# power_distribution_3_16_17.net
KiCad netlist of a schematic drawn in EAGLE
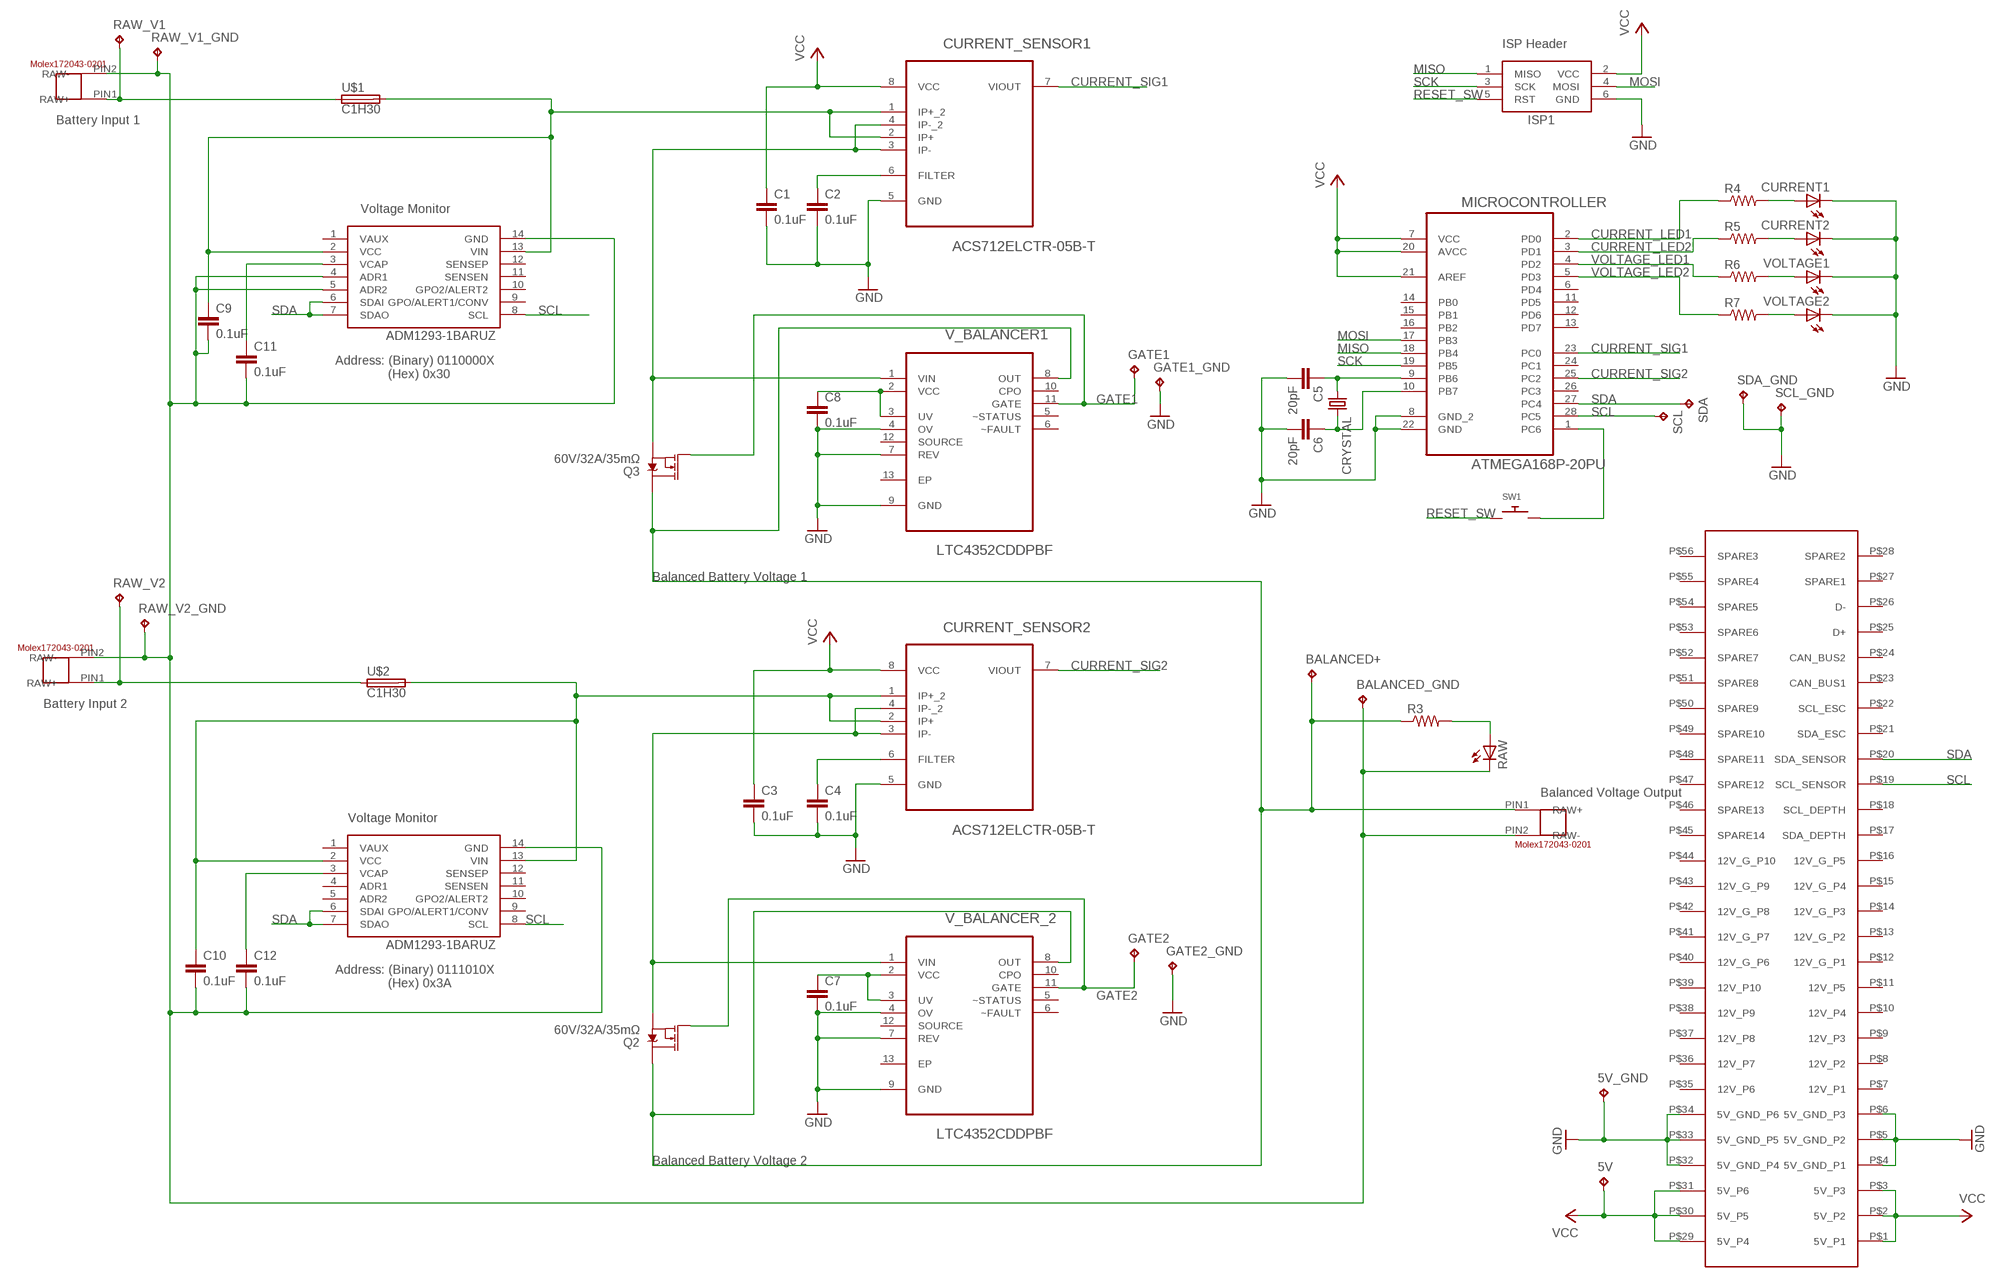
[diagram p0: schematic, sheet 1]

(export (version "E")
  (design (tool "Eeschema 10.0.6"))
  (components
    (comp (ref "5V")
      (value "TPPAD1-13")
      (footprint "eagle-import:P1-13")
      (libsource (lib "eagle-import") (part "TPPAD1-13"))
    )
    (comp (ref "5V_GND")
      (value "TPPAD1-13")
      (footprint "eagle-import:P1-13")
      (libsource (lib "eagle-import") (part "TPPAD1-13"))
    )
    (comp (ref "BALANCED+")
      (value "TPPAD1-13")
      (footprint "eagle-import:P1-13")
      (libsource (lib "eagle-import") (part "TPPAD1-13"))
    )
    (comp (ref "BALANCED_GND")
      (value "TPPAD1-13")
      (footprint "eagle-import:P1-13")
      (libsource (lib "eagle-import") (part "TPPAD1-13"))
    )
    (comp (ref "C1")
      (value "0.1uF")
      (footprint "eagle-import:CAP-PTH-SMALL-KIT")
      (libsource (lib "eagle-import") (part "0.1UF-KIT-EZ-50V-20%"))
    )
    (comp (ref "C2")
      (value "0.1uF")
      (footprint "eagle-import:CAP-PTH-SMALL-KIT")
      (libsource (lib "eagle-import") (part "0.1UF-KIT-EZ-50V-20%"))
    )
    (comp (ref "C3")
      (value "0.1uF")
      (footprint "eagle-import:CAP-PTH-SMALL-KIT")
      (libsource (lib "eagle-import") (part "0.1UF-KIT-EZ-50V-20%"))
    )
    (comp (ref "C4")
      (value "0.1uF")
      (footprint "eagle-import:CAP-PTH-SMALL-KIT")
      (libsource (lib "eagle-import") (part "0.1UF-KIT-EZ-50V-20%"))
    )
    (comp (ref "C5")
      (value "20pF")
      (footprint "eagle-import:CAP-PTH-SMALL-KIT")
      (libsource (lib "eagle-import") (part "0.1UF-KIT-EZ-50V-20%"))
    )
    (comp (ref "C6")
      (value "20pF")
      (footprint "eagle-import:CAP-PTH-SMALL-KIT")
      (libsource (lib "eagle-import") (part "0.1UF-KIT-EZ-50V-20%"))
    )
    (comp (ref "C7")
      (value "0.1uF")
      (footprint "eagle-import:CAP-PTH-SMALL-KIT")
      (libsource (lib "eagle-import") (part "0.1UF-KIT-EZ-50V-20%"))
    )
    (comp (ref "C8")
      (value "0.1uF")
      (footprint "eagle-import:CAP-PTH-SMALL-KIT")
      (libsource (lib "eagle-import") (part "0.1UF-KIT-EZ-50V-20%"))
    )
    (comp (ref "C9")
      (value "0.1uF")
      (footprint "eagle-import:CAP-PTH-SMALL-KIT")
      (libsource (lib "eagle-import") (part "0.1UF-KIT-EZ-50V-20%"))
    )
    (comp (ref "C10")
      (value "0.1uF")
      (footprint "eagle-import:CAP-PTH-SMALL-KIT")
      (libsource (lib "eagle-import") (part "0.1UF-KIT-EZ-50V-20%"))
    )
    (comp (ref "C11")
      (value "0.1uF")
      (footprint "eagle-import:CAP-PTH-SMALL-KIT")
      (libsource (lib "eagle-import") (part "0.1UF-KIT-EZ-50V-20%"))
    )
    (comp (ref "C12")
      (value "0.1uF")
      (footprint "eagle-import:CAP-PTH-SMALL-KIT")
      (libsource (lib "eagle-import") (part "0.1UF-KIT-EZ-50V-20%"))
    )
    (comp (ref "CRYSTAL")
      (value "CRYSTALHC49U-V")
      (footprint "eagle-import:HC49U-V")
      (libsource (lib "eagle-import") (part "CRYSTALHC49U-V"))
    )
    (comp (ref "CURRENT1")
      (value "LED3MM")
      (footprint "eagle-import:LED3MM")
      (libsource (lib "eagle-import") (part "LED3MM"))
    )
    (comp (ref "CURRENT2")
      (value "LED3MM")
      (footprint "eagle-import:LED3MM")
      (libsource (lib "eagle-import") (part "LED3MM"))
    )
    (comp (ref "CURRENT_SENSOR1")
      (value "ACS712ELCTR-05B-T")
      (footprint "eagle-import:SOIC127P600X175-8N")
      (libsource (lib "eagle-import") (part "ACS712ELCTR-05B-T"))
    )
    (comp (ref "CURRENT_SENSOR2")
      (value "ACS712ELCTR-05B-T")
      (footprint "eagle-import:SOIC127P600X175-8N")
      (libsource (lib "eagle-import") (part "ACS712ELCTR-05B-T"))
    )
    (comp (ref "GATE1")
      (value "TPPAD1-13")
      (footprint "eagle-import:P1-13")
      (libsource (lib "eagle-import") (part "TPPAD1-13"))
    )
    (comp (ref "GATE1_GND")
      (value "TPPAD1-13")
      (footprint "eagle-import:P1-13")
      (libsource (lib "eagle-import") (part "TPPAD1-13"))
    )
    (comp (ref "GATE2")
      (value "TPPAD1-13")
      (footprint "eagle-import:P1-13")
      (libsource (lib "eagle-import") (part "TPPAD1-13"))
    )
    (comp (ref "GATE2_GND")
      (value "TPPAD1-13")
      (footprint "eagle-import:P1-13")
      (libsource (lib "eagle-import") (part "TPPAD1-13"))
    )
    (comp (ref "INPUT1")
      (value "MOLEX172043-0201")
      (footprint "eagle-import:MOLEX172043-0201")
      (libsource (lib "eagle-import") (part "MOLEX172043-0201"))
    )
    (comp (ref "INPUT2")
      (value "MOLEX172043-0201")
      (footprint "eagle-import:MOLEX172043-0201")
      (libsource (lib "eagle-import") (part "MOLEX172043-0201"))
    )
    (comp (ref "ISP1")
      (value "AVRISP-6")
      (footprint "eagle-import:AVRISP")
      (libsource (lib "eagle-import") (part "AVRISP-6"))
    )
    (comp (ref "MICROCONTROLLER")
      (value "ATMEGA168P-20PU")
      (footprint "eagle-import:DIP254P762X457-28")
      (libsource (lib "eagle-import") (part "ATMEGA168P-20PU"))
    )
    (comp (ref "OUTPUT")
      (value "MOLEX172043-0201")
      (footprint "eagle-import:MOLEX172043-0201")
      (libsource (lib "eagle-import") (part "MOLEX172043-0201"))
    )
    (comp (ref "Q2")
      (value "60V/32A/35mΩ")
      (footprint "eagle-import:TO220V")
      (libsource (lib "eagle-import") (part "MOSFET-NCH-FQP30N06L"))
    )
    (comp (ref "Q3")
      (value "60V/32A/35mΩ")
      (footprint "eagle-import:TO220V")
      (libsource (lib "eagle-import") (part "MOSFET-NCH-FQP30N06L"))
    )
    (comp (ref "R3")
      (value "R-US_0207/12")
      (footprint "eagle-import:0207_12")
      (libsource (lib "eagle-import") (part "R-US_0207/12"))
    )
    (comp (ref "R4")
      (value "R-US_0207/12")
      (footprint "eagle-import:0207_12")
      (libsource (lib "eagle-import") (part "R-US_0207/12"))
    )
    (comp (ref "R5")
      (value "R-US_0207/12")
      (footprint "eagle-import:0207_12")
      (libsource (lib "eagle-import") (part "R-US_0207/12"))
    )
    (comp (ref "R6")
      (value "R-US_0207/12")
      (footprint "eagle-import:0207_12")
      (libsource (lib "eagle-import") (part "R-US_0207/12"))
    )
    (comp (ref "R7")
      (value "R-US_0207/12")
      (footprint "eagle-import:0207_12")
      (libsource (lib "eagle-import") (part "R-US_0207/12"))
    )
    (comp (ref "RAW")
      (value "LED3MM")
      (footprint "eagle-import:LED3MM")
      (libsource (lib "eagle-import") (part "LED3MM"))
    )
    (comp (ref "RAW_V1")
      (value "TPPAD1-13")
      (footprint "eagle-import:P1-13")
      (libsource (lib "eagle-import") (part "TPPAD1-13"))
    )
    (comp (ref "RAW_V1_GND")
      (value "TPPAD1-13")
      (footprint "eagle-import:P1-13")
      (libsource (lib "eagle-import") (part "TPPAD1-13"))
    )
    (comp (ref "RAW_V2")
      (value "TPPAD1-13")
      (footprint "eagle-import:P1-13")
      (libsource (lib "eagle-import") (part "TPPAD1-13"))
    )
    (comp (ref "RAW_V2_GND")
      (value "TPPAD1-13")
      (footprint "eagle-import:P1-13")
      (libsource (lib "eagle-import") (part "TPPAD1-13"))
    )
    (comp (ref "SCL")
      (value "TPPAD1-13")
      (footprint "eagle-import:P1-13")
      (libsource (lib "eagle-import") (part "TPPAD1-13"))
    )
    (comp (ref "SCL_GND")
      (value "TPPAD1-13")
      (footprint "eagle-import:P1-13")
      (libsource (lib "eagle-import") (part "TPPAD1-13"))
    )
    (comp (ref "SDA")
      (value "TPPAD1-13")
      (footprint "eagle-import:P1-13")
      (libsource (lib "eagle-import") (part "TPPAD1-13"))
    )
    (comp (ref "SDA_GND")
      (value "TPPAD1-13")
      (footprint "eagle-import:P1-13")
      (libsource (lib "eagle-import") (part "TPPAD1-13"))
    )
    (comp (ref "SW1")
      (value "SWITCH_PUSHBUTTONEVQ-PE")
      (footprint "eagle-import:TACT_PANA-EVQ")
      (libsource (lib "eagle-import") (part "SWITCH_PUSHBUTTONEVQ-PE"))
    )
    (comp (ref "U$1")
      (value "C1H30")
      (footprint "eagle-import:C1H30")
      (libsource (lib "eagle-import") (part "C1H30"))
    )
    (comp (ref "U$2")
      (value "C1H30")
      (footprint "eagle-import:C1H30")
      (libsource (lib "eagle-import") (part "C1H30"))
    )
    (comp (ref "U$3")
      (value "1-530844-7")
      (footprint "eagle-import:1-530844-7")
      (libsource (lib "eagle-import") (part "1-530844-7"))
    )
    (comp (ref "U$4")
      (value "ADM1293")
      (footprint "eagle-import:SOP65P640X120-14N")
      (libsource (lib "eagle-import") (part "ADM1293"))
    )
    (comp (ref "U$5")
      (value "ADM1293")
      (footprint "eagle-import:SOP65P640X120-14N")
      (libsource (lib "eagle-import") (part "ADM1293"))
    )
    (comp (ref "VOLTAGE1")
      (value "LED3MM")
      (footprint "eagle-import:LED3MM")
      (libsource (lib "eagle-import") (part "LED3MM"))
    )
    (comp (ref "VOLTAGE2")
      (value "LED3MM")
      (footprint "eagle-import:LED3MM")
      (libsource (lib "eagle-import") (part "LED3MM"))
    )
    (comp (ref "V_BALANCER1")
      (value "LTC4352CDDPBF")
      (footprint "eagle-import:DFN300X300X80-13N")
      (fields (field (name "MPN") "LTC4352CDD#PBF"))
      (libsource (lib "eagle-import") (part "LTC4352CDDPBF"))
    )
    (comp (ref "V_BALANCER_2")
      (value "LTC4352CDDPBF")
      (footprint "eagle-import:DFN300X300X80-13N")
      (fields (field (name "MPN") "LTC4352CDD#PBF"))
      (libsource (lib "eagle-import") (part "LTC4352CDDPBF"))
    )
  )
  (nets
    (net (code "1") (name "/CURRENT_LED1") (class "Default")
      (node (ref "MICROCONTROLLER") (pin "2") (pinfunction "PD0_2") (pintype "bidirectional"))
      (node (ref "R4") (pin "1") (pinfunction "1_1") (pintype "passive"))
    )
    (net (code "2") (name "/CURRENT_LED2") (class "Default")
      (node (ref "MICROCONTROLLER") (pin "3") (pinfunction "PD1_3") (pintype "bidirectional"))
      (node (ref "R5") (pin "1") (pinfunction "1_1") (pintype "passive"))
    )
    (net (code "3") (name "/CURRENT_SIG1") (class "Default")
      (node (ref "CURRENT_SENSOR1") (pin "7") (pinfunction "VIOUT_7") (pintype "output"))
      (node (ref "MICROCONTROLLER") (pin "23") (pinfunction "PC0_23") (pintype "bidirectional"))
    )
    (net (code "4") (name "/CURRENT_SIG2") (class "Default")
      (node (ref "CURRENT_SENSOR2") (pin "7") (pinfunction "VIOUT_7") (pintype "output"))
      (node (ref "MICROCONTROLLER") (pin "25") (pinfunction "PC2_25") (pintype "bidirectional"))
    )
    (net (code "5") (name "/GATE1") (class "Default")
      (node (ref "GATE1") (pin "TP") (pinfunction "TP_TP") (pintype "input"))
      (node (ref "Q3") (pin "1") (pinfunction "G_1") (pintype "bidirectional"))
      (node (ref "V_BALANCER1") (pin "11") (pinfunction "GATE_11") (pintype "output"))
    )
    (net (code "6") (name "/GATE2") (class "Default")
      (node (ref "GATE2") (pin "TP") (pinfunction "TP_TP") (pintype "input"))
      (node (ref "Q2") (pin "1") (pinfunction "G_1") (pintype "bidirectional"))
      (node (ref "V_BALANCER_2") (pin "11") (pinfunction "GATE_11") (pintype "output"))
    )
    (net (code "7") (name "/MISO") (class "Default")
      (node (ref "ISP1") (pin "1") (pinfunction "MISO_1") (pintype "input"))
      (node (ref "MICROCONTROLLER") (pin "18") (pinfunction "PB4_18") (pintype "bidirectional"))
    )
    (net (code "8") (name "/MOSI") (class "Default")
      (node (ref "ISP1") (pin "4") (pinfunction "MOSI_4") (pintype "output"))
      (node (ref "MICROCONTROLLER") (pin "17") (pinfunction "PB3_17") (pintype "bidirectional"))
    )
    (net (code "9") (name "/RESET_SW") (class "Default")
      (node (ref "ISP1") (pin "5") (pinfunction "RST_5") (pintype "output"))
      (node (ref "SW1") (pin "P$1") (pinfunction "P$1_P$1") (pintype "passive"))
    )
    (net (code "10") (name "/SCK") (class "Default")
      (node (ref "ISP1") (pin "3") (pinfunction "SCK_3") (pintype "output"))
      (node (ref "MICROCONTROLLER") (pin "19") (pinfunction "PB5_19") (pintype "bidirectional"))
    )
    (net (code "11") (name "/SCL") (class "Default")
      (node (ref "MICROCONTROLLER") (pin "28") (pinfunction "PC5_28") (pintype "bidirectional"))
      (node (ref "SCL") (pin "TP") (pinfunction "TP_TP") (pintype "input"))
      (node (ref "U$3") (pin "P$19") (pinfunction "SCL_SENSOR_P$19") (pintype "bidirectional"))
      (node (ref "U$4") (pin "8") (pinfunction "SCL_8") (pintype "bidirectional"))
      (node (ref "U$5") (pin "8") (pinfunction "SCL_8") (pintype "bidirectional"))
    )
    (net (code "12") (name "/SDA") (class "Default")
      (node (ref "MICROCONTROLLER") (pin "27") (pinfunction "PC4_27") (pintype "bidirectional"))
      (node (ref "SDA") (pin "TP") (pinfunction "TP_TP") (pintype "input"))
      (node (ref "U$3") (pin "P$20") (pinfunction "SDA_SENSOR_P$20") (pintype "bidirectional"))
      (node (ref "U$4") (pin "6") (pinfunction "SDAI_6") (pintype "bidirectional"))
      (node (ref "U$4") (pin "7") (pinfunction "SDAO_7") (pintype "bidirectional"))
      (node (ref "U$5") (pin "6") (pinfunction "SDAI_6") (pintype "bidirectional"))
      (node (ref "U$5") (pin "7") (pinfunction "SDAO_7") (pintype "bidirectional"))
    )
    (net (code "13") (name "/VOLTAGE_LED1") (class "Default")
      (node (ref "MICROCONTROLLER") (pin "4") (pinfunction "PD2_4") (pintype "bidirectional"))
      (node (ref "R6") (pin "1") (pinfunction "1_1") (pintype "passive"))
    )
    (net (code "14") (name "/VOLTAGE_LED2") (class "Default")
      (node (ref "MICROCONTROLLER") (pin "5") (pinfunction "PD3_5") (pintype "bidirectional"))
      (node (ref "R7") (pin "1") (pinfunction "1_1") (pintype "passive"))
    )
    (net (code "15") (name "GND") (class "Default")
      (node (ref "5V_GND") (pin "TP") (pinfunction "TP_TP") (pintype "input"))
      (node (ref "C1") (pin "2") (pinfunction "2_2") (pintype "passive"))
      (node (ref "C2") (pin "2") (pinfunction "2_2") (pintype "passive"))
      (node (ref "C3") (pin "2") (pinfunction "2_2") (pintype "passive"))
      (node (ref "C4") (pin "2") (pinfunction "2_2") (pintype "passive"))
      (node (ref "C5") (pin "2") (pinfunction "2_2") (pintype "passive"))
      (node (ref "C6") (pin "2") (pinfunction "2_2") (pintype "passive"))
      (node (ref "C7") (pin "2") (pinfunction "2_2") (pintype "passive"))
      (node (ref "C8") (pin "2") (pinfunction "2_2") (pintype "passive"))
      (node (ref "CURRENT1") (pin "K") (pinfunction "C_K") (pintype "passive"))
      (node (ref "CURRENT2") (pin "K") (pinfunction "C_K") (pintype "passive"))
      (node (ref "CURRENT_SENSOR1") (pin "5") (pinfunction "GND_5") (pintype "passive"))
      (node (ref "CURRENT_SENSOR2") (pin "5") (pinfunction "GND_5") (pintype "passive"))
      (node (ref "GATE1_GND") (pin "TP") (pinfunction "TP_TP") (pintype "input"))
      (node (ref "GATE2_GND") (pin "TP") (pinfunction "TP_TP") (pintype "input"))
      (node (ref "ISP1") (pin "6") (pinfunction "GND_6") (pintype "power_in"))
      (node (ref "MICROCONTROLLER") (pin "22") (pinfunction "GND_22") (pintype "passive"))
      (node (ref "MICROCONTROLLER") (pin "8") (pinfunction "GND_2_8") (pintype "passive"))
      (node (ref "SCL_GND") (pin "TP") (pinfunction "TP_TP") (pintype "input"))
      (node (ref "SDA_GND") (pin "TP") (pinfunction "TP_TP") (pintype "input"))
      (node (ref "U$3") (pin "P$32") (pinfunction "5V_GND_P4_P$32") (pintype "bidirectional"))
      (node (ref "U$3") (pin "P$33") (pinfunction "5V_GND_P5_P$33") (pintype "bidirectional"))
      (node (ref "U$3") (pin "P$34") (pinfunction "5V_GND_P6_P$34") (pintype "bidirectional"))
      (node (ref "U$3") (pin "P$4") (pinfunction "5V_GND_P1_P$4") (pintype "bidirectional"))
      (node (ref "U$3") (pin "P$5") (pinfunction "5V_GND_P2_P$5") (pintype "bidirectional"))
      (node (ref "U$3") (pin "P$6") (pinfunction "5V_GND_P3_P$6") (pintype "bidirectional"))
      (node (ref "VOLTAGE1") (pin "K") (pinfunction "C_K") (pintype "passive"))
      (node (ref "VOLTAGE2") (pin "K") (pinfunction "C_K") (pintype "passive"))
      (node (ref "V_BALANCER1") (pin "4") (pinfunction "OV_4") (pintype "input"))
      (node (ref "V_BALANCER1") (pin "7") (pinfunction "REV_7") (pintype "input"))
      (node (ref "V_BALANCER1") (pin "9") (pinfunction "GND_9") (pintype "passive"))
      (node (ref "V_BALANCER_2") (pin "4") (pinfunction "OV_4") (pintype "input"))
      (node (ref "V_BALANCER_2") (pin "7") (pinfunction "REV_7") (pintype "input"))
      (node (ref "V_BALANCER_2") (pin "9") (pinfunction "GND_9") (pintype "passive"))
    )
    (net (code "16") (name "Net-(CURRENT1-PadA)") (class "Default")
      (node (ref "CURRENT1") (pin "A") (pinfunction "A_A") (pintype "passive"))
      (node (ref "R4") (pin "2") (pinfunction "2_2") (pintype "passive"))
    )
    (net (code "17") (name "Net-(CURRENT2-PadA)") (class "Default")
      (node (ref "CURRENT2") (pin "A") (pinfunction "A_A") (pintype "passive"))
      (node (ref "R5") (pin "2") (pinfunction "2_2") (pintype "passive"))
    )
    (net (code "18") (name "Net-(CURRENT_SENSOR1-FILTER)") (class "Default")
      (node (ref "C2") (pin "1") (pinfunction "1_1") (pintype "passive"))
      (node (ref "CURRENT_SENSOR1") (pin "6") (pinfunction "FILTER_6") (pintype "input"))
    )
    (net (code "19") (name "Net-(CURRENT_SENSOR1-IP+)") (class "Default")
      (node (ref "C9") (pin "1") (pinfunction "1_1") (pintype "passive"))
      (node (ref "CURRENT_SENSOR1") (pin "1") (pinfunction "IP+_2_1") (pintype "input"))
      (node (ref "CURRENT_SENSOR1") (pin "2") (pinfunction "IP+_2") (pintype "input"))
      (node (ref "U$1") (pin "P$2") (pinfunction "2_P$2") (pintype "passive"))
      (node (ref "U$4") (pin "13") (pinfunction "VIN_13") (pintype "bidirectional"))
      (node (ref "U$4") (pin "2") (pinfunction "VCC_2") (pintype "bidirectional"))
    )
    (net (code "20") (name "Net-(CURRENT_SENSOR1-IP-)") (class "Default")
      (node (ref "CURRENT_SENSOR1") (pin "3") (pinfunction "IP-_3") (pintype "input"))
      (node (ref "CURRENT_SENSOR1") (pin "4") (pinfunction "IP-_2_4") (pintype "input"))
      (node (ref "Q3") (pin "3") (pinfunction "S_3") (pintype "bidirectional"))
      (node (ref "V_BALANCER1") (pin "1") (pinfunction "VIN_1") (pintype "power_in"))
    )
    (net (code "21") (name "Net-(CURRENT_SENSOR2-FILTER)") (class "Default")
      (node (ref "C4") (pin "1") (pinfunction "1_1") (pintype "passive"))
      (node (ref "CURRENT_SENSOR2") (pin "6") (pinfunction "FILTER_6") (pintype "input"))
    )
    (net (code "22") (name "Net-(CURRENT_SENSOR2-IP+)") (class "Default")
      (node (ref "C10") (pin "1") (pinfunction "1_1") (pintype "passive"))
      (node (ref "CURRENT_SENSOR2") (pin "1") (pinfunction "IP+_2_1") (pintype "input"))
      (node (ref "CURRENT_SENSOR2") (pin "2") (pinfunction "IP+_2") (pintype "input"))
      (node (ref "U$2") (pin "P$2") (pinfunction "2_P$2") (pintype "passive"))
      (node (ref "U$5") (pin "13") (pinfunction "VIN_13") (pintype "bidirectional"))
      (node (ref "U$5") (pin "2") (pinfunction "VCC_2") (pintype "bidirectional"))
    )
    (net (code "23") (name "Net-(CURRENT_SENSOR2-IP-)") (class "Default")
      (node (ref "CURRENT_SENSOR2") (pin "3") (pinfunction "IP-_3") (pintype "input"))
      (node (ref "CURRENT_SENSOR2") (pin "4") (pinfunction "IP-_2_4") (pintype "input"))
      (node (ref "Q2") (pin "3") (pinfunction "S_3") (pintype "bidirectional"))
      (node (ref "V_BALANCER_2") (pin "1") (pinfunction "VIN_1") (pintype "power_in"))
    )
    (net (code "24") (name "Net-(INPUT1-RAW+)") (class "Default")
      (node (ref "INPUT1") (pin "PIN1") (pinfunction "RAW+_PIN1") (pintype "bidirectional"))
      (node (ref "RAW_V1") (pin "TP") (pinfunction "TP_TP") (pintype "input"))
      (node (ref "U$1") (pin "P$1") (pinfunction "1_P$1") (pintype "passive"))
    )
    (net (code "25") (name "Net-(INPUT1-RAW-)") (class "Default")
      (node (ref "BALANCED_GND") (pin "TP") (pinfunction "TP_TP") (pintype "input"))
      (node (ref "C10") (pin "2") (pinfunction "2_2") (pintype "passive"))
      (node (ref "C11") (pin "2") (pinfunction "2_2") (pintype "passive"))
      (node (ref "C12") (pin "2") (pinfunction "2_2") (pintype "passive"))
      (node (ref "C9") (pin "2") (pinfunction "2_2") (pintype "passive"))
      (node (ref "INPUT1") (pin "PIN2") (pinfunction "RAW-_PIN2") (pintype "bidirectional"))
      (node (ref "INPUT2") (pin "PIN2") (pinfunction "RAW-_PIN2") (pintype "bidirectional"))
      (node (ref "OUTPUT") (pin "PIN2") (pinfunction "RAW-_PIN2") (pintype "bidirectional"))
      (node (ref "RAW") (pin "K") (pinfunction "C_K") (pintype "passive"))
      (node (ref "RAW_V1_GND") (pin "TP") (pinfunction "TP_TP") (pintype "input"))
      (node (ref "RAW_V2_GND") (pin "TP") (pinfunction "TP_TP") (pintype "input"))
      (node (ref "U$4") (pin "14") (pinfunction "GND_14") (pintype "bidirectional"))
      (node (ref "U$4") (pin "4") (pinfunction "ADR1_4") (pintype "bidirectional"))
      (node (ref "U$4") (pin "5") (pinfunction "ADR2_5") (pintype "bidirectional"))
      (node (ref "U$5") (pin "14") (pinfunction "GND_14") (pintype "bidirectional"))
    )
    (net (code "26") (name "Net-(INPUT2-RAW+)") (class "Default")
      (node (ref "INPUT2") (pin "PIN1") (pinfunction "RAW+_PIN1") (pintype "bidirectional"))
      (node (ref "RAW_V2") (pin "TP") (pinfunction "TP_TP") (pintype "input"))
      (node (ref "U$2") (pin "P$1") (pinfunction "1_P$1") (pintype "passive"))
    )
    (net (code "27") (name "Net-(MICROCONTROLLER-PB6)") (class "Default")
      (node (ref "C5") (pin "1") (pinfunction "1_1") (pintype "passive"))
      (node (ref "CRYSTAL") (pin "1") (pinfunction "1_1") (pintype "passive"))
      (node (ref "MICROCONTROLLER") (pin "9") (pinfunction "PB6_9") (pintype "bidirectional"))
    )
    (net (code "28") (name "Net-(MICROCONTROLLER-PB7)") (class "Default")
      (node (ref "C6") (pin "1") (pinfunction "1_1") (pintype "passive"))
      (node (ref "CRYSTAL") (pin "2") (pinfunction "2_2") (pintype "passive"))
      (node (ref "MICROCONTROLLER") (pin "10") (pinfunction "PB7_10") (pintype "bidirectional"))
    )
    (net (code "29") (name "Net-(MICROCONTROLLER-PC6)") (class "Default")
      (node (ref "MICROCONTROLLER") (pin "1") (pinfunction "PC6_1") (pintype "bidirectional"))
      (node (ref "SW1") (pin "P$2") (pinfunction "P$2_P$2") (pintype "passive"))
    )
    (net (code "30") (name "Net-(OUTPUT-RAW+)") (class "Default")
      (node (ref "BALANCED+") (pin "TP") (pinfunction "TP_TP") (pintype "input"))
      (node (ref "OUTPUT") (pin "PIN1") (pinfunction "RAW+_PIN1") (pintype "bidirectional"))
      (node (ref "Q2") (pin "2") (pinfunction "D_2") (pintype "bidirectional"))
      (node (ref "Q3") (pin "2") (pinfunction "D_2") (pintype "bidirectional"))
      (node (ref "R3") (pin "1") (pinfunction "1_1") (pintype "passive"))
      (node (ref "V_BALANCER1") (pin "8") (pinfunction "OUT_8") (pintype "output"))
      (node (ref "V_BALANCER_2") (pin "8") (pinfunction "OUT_8") (pintype "output"))
    )
    (net (code "31") (name "Net-(R3-Pad2)") (class "Default")
      (node (ref "R3") (pin "2") (pinfunction "2_2") (pintype "passive"))
      (node (ref "RAW") (pin "A") (pinfunction "A_A") (pintype "passive"))
    )
    (net (code "32") (name "Net-(R6-Pad2)") (class "Default")
      (node (ref "R6") (pin "2") (pinfunction "2_2") (pintype "passive"))
      (node (ref "VOLTAGE1") (pin "A") (pinfunction "A_A") (pintype "passive"))
    )
    (net (code "33") (name "Net-(R7-Pad2)") (class "Default")
      (node (ref "R7") (pin "2") (pinfunction "2_2") (pintype "passive"))
      (node (ref "VOLTAGE2") (pin "A") (pinfunction "A_A") (pintype "passive"))
    )
    (net (code "34") (name "Net-(U$4-VCAP)") (class "Default")
      (node (ref "C11") (pin "1") (pinfunction "1_1") (pintype "passive"))
      (node (ref "U$4") (pin "3") (pinfunction "VCAP_3") (pintype "bidirectional"))
    )
    (net (code "35") (name "Net-(U$5-VCAP)") (class "Default")
      (node (ref "C12") (pin "1") (pinfunction "1_1") (pintype "passive"))
      (node (ref "U$5") (pin "3") (pinfunction "VCAP_3") (pintype "bidirectional"))
    )
    (net (code "36") (name "Net-(V_BALANCER1-UV)") (class "Default")
      (node (ref "C8") (pin "1") (pinfunction "1_1") (pintype "passive"))
      (node (ref "V_BALANCER1") (pin "2") (pinfunction "VCC_2") (pintype "power_in"))
      (node (ref "V_BALANCER1") (pin "3") (pinfunction "UV_3") (pintype "input"))
    )
    (net (code "37") (name "Net-(V_BALANCER_2-UV)") (class "Default")
      (node (ref "C7") (pin "1") (pinfunction "1_1") (pintype "passive"))
      (node (ref "V_BALANCER_2") (pin "2") (pinfunction "VCC_2") (pintype "power_in"))
      (node (ref "V_BALANCER_2") (pin "3") (pinfunction "UV_3") (pintype "input"))
    )
    (net (code "38") (name "VCC") (class "Default")
      (node (ref "5V") (pin "TP") (pinfunction "TP_TP") (pintype "input"))
      (node (ref "C1") (pin "1") (pinfunction "1_1") (pintype "passive"))
      (node (ref "C3") (pin "1") (pinfunction "1_1") (pintype "passive"))
      (node (ref "CURRENT_SENSOR1") (pin "8") (pinfunction "VCC_8") (pintype "power_in"))
      (node (ref "CURRENT_SENSOR2") (pin "8") (pinfunction "VCC_8") (pintype "power_in"))
      (node (ref "ISP1") (pin "2") (pinfunction "VCC_2") (pintype "power_in"))
      (node (ref "MICROCONTROLLER") (pin "20") (pinfunction "AVCC_20") (pintype "power_in"))
      (node (ref "MICROCONTROLLER") (pin "21") (pinfunction "AREF_21") (pintype "input"))
      (node (ref "MICROCONTROLLER") (pin "7") (pinfunction "VCC_7") (pintype "power_in"))
      (node (ref "U$3") (pin "P$1") (pinfunction "5V_P1_P$1") (pintype "bidirectional"))
      (node (ref "U$3") (pin "P$2") (pinfunction "5V_P2_P$2") (pintype "bidirectional"))
      (node (ref "U$3") (pin "P$29") (pinfunction "5V_P4_P$29") (pintype "bidirectional"))
      (node (ref "U$3") (pin "P$3") (pinfunction "5V_P3_P$3") (pintype "bidirectional"))
      (node (ref "U$3") (pin "P$30") (pinfunction "5V_P5_P$30") (pintype "bidirectional"))
      (node (ref "U$3") (pin "P$31") (pinfunction "5V_P6_P$31") (pintype "bidirectional"))
    )
    (net (code "39") (name "unconnected-(MICROCONTROLLER-PB0-Pad14)") (class "Default")
      (node (ref "MICROCONTROLLER") (pin "14") (pinfunction "PB0_14") (pintype "bidirectional"))
    )
    (net (code "40") (name "unconnected-(MICROCONTROLLER-PB1-Pad15)") (class "Default")
      (node (ref "MICROCONTROLLER") (pin "15") (pinfunction "PB1_15") (pintype "bidirectional"))
    )
    (net (code "41") (name "unconnected-(MICROCONTROLLER-PB2-Pad16)") (class "Default")
      (node (ref "MICROCONTROLLER") (pin "16") (pinfunction "PB2_16") (pintype "bidirectional"))
    )
    (net (code "42") (name "unconnected-(MICROCONTROLLER-PC1-Pad24)") (class "Default")
      (node (ref "MICROCONTROLLER") (pin "24") (pinfunction "PC1_24") (pintype "bidirectional"))
    )
    (net (code "43") (name "unconnected-(MICROCONTROLLER-PC3-Pad26)") (class "Default")
      (node (ref "MICROCONTROLLER") (pin "26") (pinfunction "PC3_26") (pintype "bidirectional"))
    )
    (net (code "44") (name "unconnected-(MICROCONTROLLER-PD4-Pad6)") (class "Default")
      (node (ref "MICROCONTROLLER") (pin "6") (pinfunction "PD4_6") (pintype "bidirectional"))
    )
    (net (code "45") (name "unconnected-(MICROCONTROLLER-PD5-Pad11)") (class "Default")
      (node (ref "MICROCONTROLLER") (pin "11") (pinfunction "PD5_11") (pintype "bidirectional"))
    )
    (net (code "46") (name "unconnected-(MICROCONTROLLER-PD6-Pad12)") (class "Default")
      (node (ref "MICROCONTROLLER") (pin "12") (pinfunction "PD6_12") (pintype "bidirectional"))
    )
    (net (code "47") (name "unconnected-(MICROCONTROLLER-PD7-Pad13)") (class "Default")
      (node (ref "MICROCONTROLLER") (pin "13") (pinfunction "PD7_13") (pintype "bidirectional"))
    )
    (net (code "48") (name "unconnected-(U$3-12V_G_P1-PadP$12)") (class "Default")
      (node (ref "U$3") (pin "P$12") (pinfunction "12V_G_P1_P$12") (pintype "bidirectional"))
    )
    (net (code "49") (name "unconnected-(U$3-12V_G_P2-PadP$13)") (class "Default")
      (node (ref "U$3") (pin "P$13") (pinfunction "12V_G_P2_P$13") (pintype "bidirectional"))
    )
    (net (code "50") (name "unconnected-(U$3-12V_G_P3-PadP$14)") (class "Default")
      (node (ref "U$3") (pin "P$14") (pinfunction "12V_G_P3_P$14") (pintype "bidirectional"))
    )
    (net (code "51") (name "unconnected-(U$3-12V_G_P4-PadP$15)") (class "Default")
      (node (ref "U$3") (pin "P$15") (pinfunction "12V_G_P4_P$15") (pintype "bidirectional"))
    )
    (net (code "52") (name "unconnected-(U$3-12V_G_P5-PadP$16)") (class "Default")
      (node (ref "U$3") (pin "P$16") (pinfunction "12V_G_P5_P$16") (pintype "bidirectional"))
    )
    (net (code "53") (name "unconnected-(U$3-12V_G_P6-PadP$40)") (class "Default")
      (node (ref "U$3") (pin "P$40") (pinfunction "12V_G_P6_P$40") (pintype "bidirectional"))
    )
    (net (code "54") (name "unconnected-(U$3-12V_G_P7-PadP$41)") (class "Default")
      (node (ref "U$3") (pin "P$41") (pinfunction "12V_G_P7_P$41") (pintype "bidirectional"))
    )
    (net (code "55") (name "unconnected-(U$3-12V_G_P8-PadP$42)") (class "Default")
      (node (ref "U$3") (pin "P$42") (pinfunction "12V_G_P8_P$42") (pintype "bidirectional"))
    )
    (net (code "56") (name "unconnected-(U$3-12V_G_P9-PadP$43)") (class "Default")
      (node (ref "U$3") (pin "P$43") (pinfunction "12V_G_P9_P$43") (pintype "bidirectional"))
    )
    (net (code "57") (name "unconnected-(U$3-12V_G_P10-PadP$44)") (class "Default")
      (node (ref "U$3") (pin "P$44") (pinfunction "12V_G_P10_P$44") (pintype "bidirectional"))
    )
    (net (code "58") (name "unconnected-(U$3-12V_P1-PadP$7)") (class "Default")
      (node (ref "U$3") (pin "P$7") (pinfunction "12V_P1_P$7") (pintype "bidirectional"))
    )
    (net (code "59") (name "unconnected-(U$3-12V_P2-PadP$8)") (class "Default")
      (node (ref "U$3") (pin "P$8") (pinfunction "12V_P2_P$8") (pintype "bidirectional"))
    )
    (net (code "60") (name "unconnected-(U$3-12V_P3-PadP$9)") (class "Default")
      (node (ref "U$3") (pin "P$9") (pinfunction "12V_P3_P$9") (pintype "bidirectional"))
    )
    (net (code "61") (name "unconnected-(U$3-12V_P4-PadP$10)") (class "Default")
      (node (ref "U$3") (pin "P$10") (pinfunction "12V_P4_P$10") (pintype "bidirectional"))
    )
    (net (code "62") (name "unconnected-(U$3-12V_P5-PadP$11)") (class "Default")
      (node (ref "U$3") (pin "P$11") (pinfunction "12V_P5_P$11") (pintype "bidirectional"))
    )
    (net (code "63") (name "unconnected-(U$3-12V_P6-PadP$35)") (class "Default")
      (node (ref "U$3") (pin "P$35") (pinfunction "12V_P6_P$35") (pintype "bidirectional"))
    )
    (net (code "64") (name "unconnected-(U$3-12V_P7-PadP$36)") (class "Default")
      (node (ref "U$3") (pin "P$36") (pinfunction "12V_P7_P$36") (pintype "bidirectional"))
    )
    (net (code "65") (name "unconnected-(U$3-12V_P8-PadP$37)") (class "Default")
      (node (ref "U$3") (pin "P$37") (pinfunction "12V_P8_P$37") (pintype "bidirectional"))
    )
    (net (code "66") (name "unconnected-(U$3-12V_P9-PadP$38)") (class "Default")
      (node (ref "U$3") (pin "P$38") (pinfunction "12V_P9_P$38") (pintype "bidirectional"))
    )
    (net (code "67") (name "unconnected-(U$3-12V_P10-PadP$39)") (class "Default")
      (node (ref "U$3") (pin "P$39") (pinfunction "12V_P10_P$39") (pintype "bidirectional"))
    )
    (net (code "68") (name "unconnected-(U$3-CAN_BUS1-PadP$23)") (class "Default")
      (node (ref "U$3") (pin "P$23") (pinfunction "CAN_BUS1_P$23") (pintype "bidirectional"))
    )
    (net (code "69") (name "unconnected-(U$3-CAN_BUS2-PadP$24)") (class "Default")
      (node (ref "U$3") (pin "P$24") (pinfunction "CAN_BUS2_P$24") (pintype "bidirectional"))
    )
    (net (code "70") (name "unconnected-(U$3-D+-PadP$25)") (class "Default")
      (node (ref "U$3") (pin "P$25") (pinfunction "D+_P$25") (pintype "bidirectional"))
    )
    (net (code "71") (name "unconnected-(U$3-D--PadP$26)") (class "Default")
      (node (ref "U$3") (pin "P$26") (pinfunction "D-_P$26") (pintype "bidirectional"))
    )
    (net (code "72") (name "unconnected-(U$3-SCL_DEPTH-PadP$18)") (class "Default")
      (node (ref "U$3") (pin "P$18") (pinfunction "SCL_DEPTH_P$18") (pintype "bidirectional"))
    )
    (net (code "73") (name "unconnected-(U$3-SCL_ESC-PadP$22)") (class "Default")
      (node (ref "U$3") (pin "P$22") (pinfunction "SCL_ESC_P$22") (pintype "bidirectional"))
    )
    (net (code "74") (name "unconnected-(U$3-SDA_DEPTH-PadP$17)") (class "Default")
      (node (ref "U$3") (pin "P$17") (pinfunction "SDA_DEPTH_P$17") (pintype "bidirectional"))
    )
    (net (code "75") (name "unconnected-(U$3-SDA_ESC-PadP$21)") (class "Default")
      (node (ref "U$3") (pin "P$21") (pinfunction "SDA_ESC_P$21") (pintype "bidirectional"))
    )
    (net (code "76") (name "unconnected-(U$3-SPARE1-PadP$27)") (class "Default")
      (node (ref "U$3") (pin "P$27") (pinfunction "SPARE1_P$27") (pintype "bidirectional"))
    )
    (net (code "77") (name "unconnected-(U$3-SPARE2-PadP$28)") (class "Default")
      (node (ref "U$3") (pin "P$28") (pinfunction "SPARE2_P$28") (pintype "bidirectional"))
    )
    (net (code "78") (name "unconnected-(U$3-SPARE3-PadP$56)") (class "Default")
      (node (ref "U$3") (pin "P$56") (pinfunction "SPARE3_P$56") (pintype "bidirectional"))
    )
    (net (code "79") (name "unconnected-(U$3-SPARE4-PadP$55)") (class "Default")
      (node (ref "U$3") (pin "P$55") (pinfunction "SPARE4_P$55") (pintype "bidirectional"))
    )
    (net (code "80") (name "unconnected-(U$3-SPARE5-PadP$54)") (class "Default")
      (node (ref "U$3") (pin "P$54") (pinfunction "SPARE5_P$54") (pintype "bidirectional"))
    )
    (net (code "81") (name "unconnected-(U$3-SPARE6-PadP$53)") (class "Default")
      (node (ref "U$3") (pin "P$53") (pinfunction "SPARE6_P$53") (pintype "bidirectional"))
    )
    (net (code "82") (name "unconnected-(U$3-SPARE7-PadP$52)") (class "Default")
      (node (ref "U$3") (pin "P$52") (pinfunction "SPARE7_P$52") (pintype "bidirectional"))
    )
    (net (code "83") (name "unconnected-(U$3-SPARE8-PadP$51)") (class "Default")
      (node (ref "U$3") (pin "P$51") (pinfunction "SPARE8_P$51") (pintype "bidirectional"))
    )
    (net (code "84") (name "unconnected-(U$3-SPARE9-PadP$50)") (class "Default")
      (node (ref "U$3") (pin "P$50") (pinfunction "SPARE9_P$50") (pintype "bidirectional"))
    )
    (net (code "85") (name "unconnected-(U$3-SPARE10-PadP$49)") (class "Default")
      (node (ref "U$3") (pin "P$49") (pinfunction "SPARE10_P$49") (pintype "bidirectional"))
    )
    (net (code "86") (name "unconnected-(U$3-SPARE11-PadP$48)") (class "Default")
      (node (ref "U$3") (pin "P$48") (pinfunction "SPARE11_P$48") (pintype "bidirectional"))
    )
    (net (code "87") (name "unconnected-(U$3-SPARE12-PadP$47)") (class "Default")
      (node (ref "U$3") (pin "P$47") (pinfunction "SPARE12_P$47") (pintype "bidirectional"))
    )
    (net (code "88") (name "unconnected-(U$3-SPARE13-PadP$46)") (class "Default")
      (node (ref "U$3") (pin "P$46") (pinfunction "SPARE13_P$46") (pintype "bidirectional"))
    )
    (net (code "89") (name "unconnected-(U$3-SPARE14-PadP$45)") (class "Default")
      (node (ref "U$3") (pin "P$45") (pinfunction "SPARE14_P$45") (pintype "bidirectional"))
    )
    (net (code "90") (name "unconnected-(U$4-GPO2{slash}ALERT2-Pad10)") (class "Default")
      (node (ref "U$4") (pin "10") (pinfunction "GPO2/ALERT2_10") (pintype "bidirectional"))
    )
    (net (code "91") (name "unconnected-(U$4-GPO{slash}ALERT1{slash}CONV-Pad9)") (class "Default")
      (node (ref "U$4") (pin "9") (pinfunction "GPO/ALERT1/CONV_9") (pintype "bidirectional"))
    )
    (net (code "92") (name "unconnected-(U$4-SENSEN-Pad11)") (class "Default")
      (node (ref "U$4") (pin "11") (pinfunction "SENSEN_11") (pintype "bidirectional"))
    )
    (net (code "93") (name "unconnected-(U$4-SENSEP-Pad12)") (class "Default")
      (node (ref "U$4") (pin "12") (pinfunction "SENSEP_12") (pintype "bidirectional"))
    )
    (net (code "94") (name "unconnected-(U$4-VAUX-Pad1)") (class "Default")
      (node (ref "U$4") (pin "1") (pinfunction "VAUX_1") (pintype "bidirectional"))
    )
    (net (code "95") (name "unconnected-(U$5-ADR1-Pad4)") (class "Default")
      (node (ref "U$5") (pin "4") (pinfunction "ADR1_4") (pintype "bidirectional"))
    )
    (net (code "96") (name "unconnected-(U$5-ADR2-Pad5)") (class "Default")
      (node (ref "U$5") (pin "5") (pinfunction "ADR2_5") (pintype "bidirectional"))
    )
    (net (code "97") (name "unconnected-(U$5-GPO2{slash}ALERT2-Pad10)") (class "Default")
      (node (ref "U$5") (pin "10") (pinfunction "GPO2/ALERT2_10") (pintype "bidirectional"))
    )
    (net (code "98") (name "unconnected-(U$5-GPO{slash}ALERT1{slash}CONV-Pad9)") (class "Default")
      (node (ref "U$5") (pin "9") (pinfunction "GPO/ALERT1/CONV_9") (pintype "bidirectional"))
    )
    (net (code "99") (name "unconnected-(U$5-SENSEN-Pad11)") (class "Default")
      (node (ref "U$5") (pin "11") (pinfunction "SENSEN_11") (pintype "bidirectional"))
    )
    (net (code "100") (name "unconnected-(U$5-SENSEP-Pad12)") (class "Default")
      (node (ref "U$5") (pin "12") (pinfunction "SENSEP_12") (pintype "bidirectional"))
    )
    (net (code "101") (name "unconnected-(U$5-VAUX-Pad1)") (class "Default")
      (node (ref "U$5") (pin "1") (pinfunction "VAUX_1") (pintype "bidirectional"))
    )
    (net (code "102") (name "unconnected-(V_BALANCER1-CPO-Pad10)") (class "Default")
      (node (ref "V_BALANCER1") (pin "10") (pinfunction "CPO_10") (pintype "output"))
    )
    (net (code "103") (name "unconnected-(V_BALANCER1-EP-Pad13)") (class "Default")
      (node (ref "V_BALANCER1") (pin "13") (pinfunction "EP_13") (pintype "passive"))
    )
    (net (code "104") (name "unconnected-(V_BALANCER1-SOURCE-Pad12)") (class "Default")
      (node (ref "V_BALANCER1") (pin "12") (pinfunction "SOURCE_12") (pintype "input"))
    )
    (net (code "105") (name "unconnected-(V_BALANCER1-~{FAULT}-Pad6)") (class "Default")
      (node (ref "V_BALANCER1") (pin "6") (pinfunction "~{FAULT}_6") (pintype "output"))
    )
    (net (code "106") (name "unconnected-(V_BALANCER1-~{STATUS}-Pad5)") (class "Default")
      (node (ref "V_BALANCER1") (pin "5") (pinfunction "~{STATUS}_5") (pintype "output"))
    )
    (net (code "107") (name "unconnected-(V_BALANCER_2-CPO-Pad10)") (class "Default")
      (node (ref "V_BALANCER_2") (pin "10") (pinfunction "CPO_10") (pintype "output"))
    )
    (net (code "108") (name "unconnected-(V_BALANCER_2-EP-Pad13)") (class "Default")
      (node (ref "V_BALANCER_2") (pin "13") (pinfunction "EP_13") (pintype "passive"))
    )
    (net (code "109") (name "unconnected-(V_BALANCER_2-SOURCE-Pad12)") (class "Default")
      (node (ref "V_BALANCER_2") (pin "12") (pinfunction "SOURCE_12") (pintype "input"))
    )
    (net (code "110") (name "unconnected-(V_BALANCER_2-~{FAULT}-Pad6)") (class "Default")
      (node (ref "V_BALANCER_2") (pin "6") (pinfunction "~{FAULT}_6") (pintype "output"))
    )
    (net (code "111") (name "unconnected-(V_BALANCER_2-~{STATUS}-Pad5)") (class "Default")
      (node (ref "V_BALANCER_2") (pin "5") (pinfunction "~{STATUS}_5") (pintype "output"))
    )
  )
)
